# Copy_of_SolderingStation_Control_-_PUMD2.net
KiCad netlist of a schematic drawn in Altium Designer
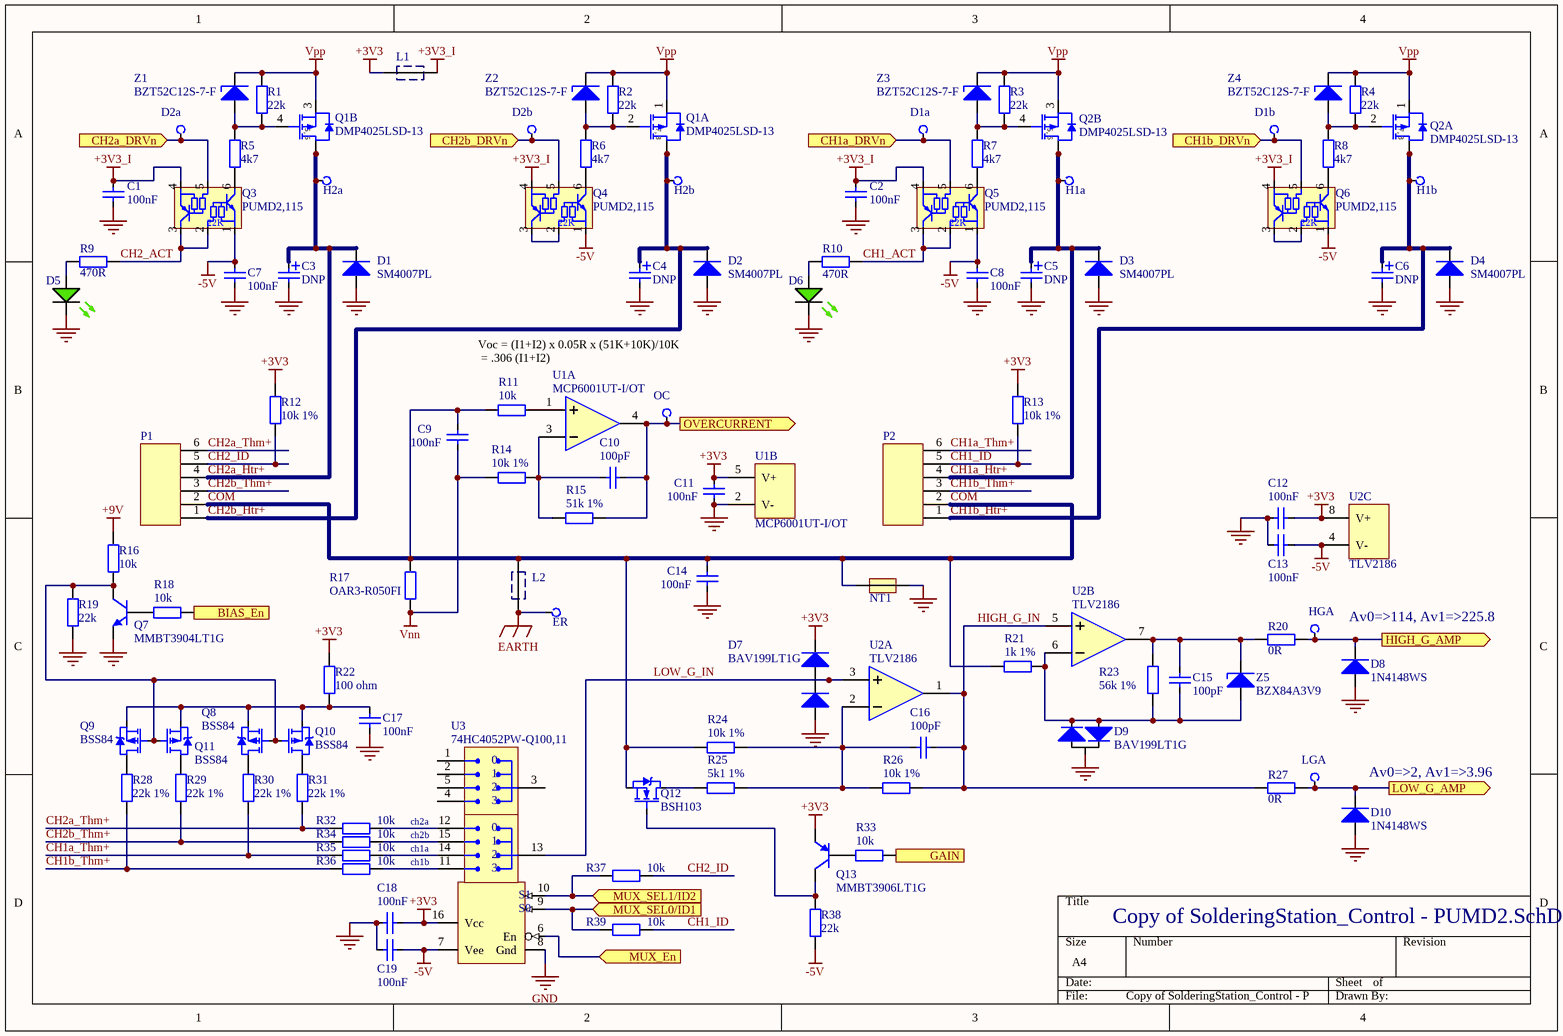
[diagram p0: Copy of SolderingStation_Control - PUMD2.SchDoc]

(export (version "E")
  (design (tool "Eeschema 10.0.6"))
  (components
    (comp (ref "C1")
      (value "100nF")
      (footprint "CCNP1608-0603")
      (description "Capacitor non-polar SMT 0603")
      (fields
        (field (name "MANUFACTURER") "Generic Components")
        (field (name "PUBLISHER") "Altium Hobart Technology Centre")
      )
      (libsource (lib "MyLibrary") (part "Cap_CCNP_0603"))
    )
    (comp (ref "C2")
      (value "100nF")
      (footprint "CCNP1608-0603")
      (description "Capacitor non-polar SMT 0603")
      (fields
        (field (name "MANUFACTURER") "Generic Components")
        (field (name "PUBLISHER") "Altium Hobart Technology Centre")
      )
      (libsource (lib "MyLibrary") (part "Cap_CCNP_0603"))
    )
    (comp (ref "C3")
      (value "DNP")
      (footprint "CC2012-0805")
      (description "Capacitor SMT 0805")
      (fields
        (field (name "MANUFACTURER") "Generic Components")
        (field (name "PUBLISHER") "Altium Hobart Technology Centre")
      )
      (libsource (lib "MyLibrary") (part "Cap_CC_0805"))
    )
    (comp (ref "C4")
      (value "DNP")
      (footprint "CC2012-0805")
      (description "Capacitor SMT 0805")
      (fields
        (field (name "MANUFACTURER") "Generic Components")
        (field (name "PUBLISHER") "Altium Hobart Technology Centre")
      )
      (libsource (lib "MyLibrary") (part "Cap_CC_0805"))
    )
    (comp (ref "C5")
      (value "DNP")
      (footprint "CC2012-0805")
      (description "Capacitor SMT 0805")
      (fields
        (field (name "MANUFACTURER") "Generic Components")
        (field (name "PUBLISHER") "Altium Hobart Technology Centre")
      )
      (libsource (lib "MyLibrary") (part "Cap_CC_0805"))
    )
    (comp (ref "C6")
      (value "DNP")
      (footprint "CC2012-0805")
      (description "Capacitor SMT 0805")
      (fields
        (field (name "MANUFACTURER") "Generic Components")
        (field (name "PUBLISHER") "Altium Hobart Technology Centre")
      )
      (libsource (lib "MyLibrary") (part "Cap_CC_0805"))
    )
    (comp (ref "C7")
      (value "100nF")
      (footprint "CCNP1608-0603")
      (description "Capacitor non-polar SMT 0603")
      (fields
        (field (name "MANUFACTURER") "Generic Components")
        (field (name "PUBLISHER") "Altium Hobart Technology Centre")
      )
      (libsource (lib "MyLibrary") (part "Cap_CCNP_0603"))
    )
    (comp (ref "C8")
      (value "100nF")
      (footprint "CCNP1608-0603")
      (description "Capacitor non-polar SMT 0603")
      (fields
        (field (name "MANUFACTURER") "Generic Components")
        (field (name "PUBLISHER") "Altium Hobart Technology Centre")
      )
      (libsource (lib "MyLibrary") (part "Cap_CCNP_0603"))
    )
    (comp (ref "C9")
      (value "100nF")
      (footprint "CCNP1608-0603")
      (description "Capacitor non-polar SMT 0603")
      (fields
        (field (name "MANUFACTURER") "Generic Components")
        (field (name "PUBLISHER") "Altium Hobart Technology Centre")
      )
      (libsource (lib "MyLibrary") (part "Cap_CCNP_0603"))
    )
    (comp (ref "C10")
      (value "100pF")
      (footprint "CCNP1608-0603")
      (description "Capacitor non-polar SMT 0603")
      (fields
        (field (name "MANUFACTURER") "Generic Components")
        (field (name "PUBLISHER") "Altium Hobart Technology Centre")
      )
      (libsource (lib "MyLibrary") (part "Cap_CCNP_0603"))
    )
    (comp (ref "C11")
      (value "100nF")
      (footprint "CCNP1608-0603")
      (description "Capacitor non-polar SMT 0603")
      (fields
        (field (name "MANUFACTURER") "Generic Components")
        (field (name "PUBLISHER") "Altium Hobart Technology Centre")
      )
      (libsource (lib "MyLibrary") (part "Cap_CCNP_0603"))
    )
    (comp (ref "C12")
      (value "100nF")
      (footprint "CCNP1608-0603")
      (description "Capacitor non-polar SMT 0603")
      (fields
        (field (name "MANUFACTURER") "Generic Components")
        (field (name "PUBLISHER") "Altium Hobart Technology Centre")
      )
      (libsource (lib "MyLibrary") (part "Cap_CCNP_0603"))
    )
    (comp (ref "C13")
      (value "100nF")
      (footprint "CCNP1608-0603")
      (description "Capacitor non-polar SMT 0603")
      (fields
        (field (name "MANUFACTURER") "Generic Components")
        (field (name "PUBLISHER") "Altium Hobart Technology Centre")
      )
      (libsource (lib "MyLibrary") (part "Cap_CCNP_0603"))
    )
    (comp (ref "C14")
      (value "100nF")
      (footprint "CCNP1608-0603")
      (description "Capacitor non-polar SMT 0603")
      (fields
        (field (name "MANUFACTURER") "Generic Components")
        (field (name "PUBLISHER") "Altium Hobart Technology Centre")
      )
      (libsource (lib "MyLibrary") (part "Cap_CCNP_0603"))
    )
    (comp (ref "C15")
      (value "100pF")
      (footprint "CCNP1608-0603")
      (description "Capacitor non-polar SMT 0603")
      (fields
        (field (name "MANUFACTURER") "Generic Components")
        (field (name "PUBLISHER") "Altium Hobart Technology Centre")
      )
      (libsource (lib "MyLibrary") (part "Cap_CCNP_0603"))
    )
    (comp (ref "C16")
      (value "100pF")
      (footprint "CCNP1608-0603")
      (description "Capacitor non-polar SMT 0603")
      (fields
        (field (name "MANUFACTURER") "Generic Components")
        (field (name "PUBLISHER") "Altium Hobart Technology Centre")
      )
      (libsource (lib "MyLibrary") (part "Cap_CCNP_0603"))
    )
    (comp (ref "C17")
      (value "100nF")
      (footprint "CCNP1608-0603")
      (description "Capacitor non-polar SMT 0603")
      (fields
        (field (name "MANUFACTURER") "Generic Components")
        (field (name "PUBLISHER") "Altium Hobart Technology Centre")
      )
      (libsource (lib "MyLibrary") (part "Cap_CCNP_0603"))
    )
    (comp (ref "C18")
      (value "100nF")
      (footprint "CCNP1608-0603")
      (description "Capacitor non-polar SMT 0603")
      (fields
        (field (name "MANUFACTURER") "Generic Components")
        (field (name "PUBLISHER") "Altium Hobart Technology Centre")
      )
      (libsource (lib "MyLibrary") (part "Cap_CCNP_0603"))
    )
    (comp (ref "C19")
      (value "100nF")
      (footprint "CCNP1608-0603")
      (description "Capacitor non-polar SMT 0603")
      (fields
        (field (name "MANUFACTURER") "Generic Components")
        (field (name "PUBLISHER") "Altium Hobart Technology Centre")
      )
      (libsource (lib "MyLibrary") (part "Cap_CCNP_0603"))
    )
    (comp (ref "D1")
      (value "SM4007PL")
      (footprint "SOD-123FL")
      (description "Diodes - General Purpose, 1kV 1A 1.1V 1A SOD-123FL")
      (libsource (lib "MyLibrary") (part "SM4007PL"))
    )
    (comp (ref "D1a")
      (value "Drive1")
      (footprint "PCBPIN - 0.7mm")
      (description "Test Point")
      (libsource (lib "MyLibrary") (part "TP"))
    )
    (comp (ref "D1b")
      (value "Drive2")
      (footprint "PCBPIN - 0.7mm")
      (description "Test Point")
      (libsource (lib "MyLibrary") (part "TP"))
    )
    (comp (ref "D2")
      (value "SM4007PL")
      (footprint "SOD-123FL")
      (description "Diodes - General Purpose, 1kV 1A 1.1V 1A SOD-123FL")
      (libsource (lib "MyLibrary") (part "SM4007PL"))
    )
    (comp (ref "D2a")
      (value "Drive2")
      (footprint "PCBPIN - 0.7mm")
      (description "Test Point")
      (libsource (lib "MyLibrary") (part "TP"))
    )
    (comp (ref "D2b")
      (value "Drive2")
      (footprint "PCBPIN - 0.7mm")
      (description "Test Point")
      (libsource (lib "MyLibrary") (part "TP"))
    )
    (comp (ref "D3")
      (value "SM4007PL")
      (footprint "SOD-123FL")
      (description "Diodes - General Purpose, 1kV 1A 1.1V 1A SOD-123FL")
      (libsource (lib "MyLibrary") (part "SM4007PL"))
    )
    (comp (ref "D4")
      (value "SM4007PL")
      (footprint "SOD-123FL")
      (description "Diodes - General Purpose, 1kV 1A 1.1V 1A SOD-123FL")
      (libsource (lib "MyLibrary") (part "SM4007PL"))
    )
    (comp (ref "D5")
      (value "LED")
      (footprint "LED3MM-GREEN - 10mm Proud")
      (description "3mm Green LED")
      (fields (field (name "MANUFACTURER") "Generic Components") (field (name "PUBLISHER") "Altium Limited"))
      (libsource (lib "MySchLib") (part "LED_3MM_GREEN"))
    )
    (comp (ref "D6")
      (value "LED")
      (footprint "LED3MM-GREEN - 10mm Proud")
      (description "3mm Green LED")
      (fields (field (name "MANUFACTURER") "Generic Components") (field (name "PUBLISHER") "Altium Limited"))
      (libsource (lib "MySchLib") (part "LED_3MM_GREEN"))
    )
    (comp (ref "D7")
      (value "BAV199LT1G")
      (footprint "SOT23_M")
      (description "Dual Series low-leakage switching diodes, 3-Pin SOT-23")
      (libsource (lib "MySchLib") (part "BAV199LT1G"))
    )
    (comp (ref "D8")
      (value "1N4148WS")
      (footprint "SOD-323")
      (description "Switching Diode 100V 150mA 1.25V@150mA 4ns SOD-323")
      (libsource (lib "MyLibrary") (part "1N4148WS"))
    )
    (comp (ref "D9")
      (value "BAV199LT1G")
      (footprint "SOT23_M")
      (description "Dual Series low-leakage switching diodes, 3-Pin SOT-23")
      (libsource (lib "MyLibrary") (part "BAV199LT1G"))
    )
    (comp (ref "D10")
      (value "1N4148WS")
      (footprint "SOD-323")
      (description "Switching Diode 100V 150mA 1.25V@150mA 4ns SOD-323")
      (libsource (lib "MyLibrary") (part "1N4148WS"))
    )
    (comp (ref "ER")
      (value "Gnd")
      (footprint "PCBPIN - 1mm")
      (description "Test Point")
      (libsource (lib "") (part "TP_1"))
    )
    (comp (ref "H1a")
      (value "Heater1")
      (footprint "PCBPIN - 0.7mm")
      (description "Test Point")
      (libsource (lib "") (part "TP_1"))
    )
    (comp (ref "H1b")
      (value "Heater2")
      (footprint "PCBPIN - 0.7mm")
      (description "Test Point")
      (libsource (lib "") (part "TP_1"))
    )
    (comp (ref "H2a")
      (value "Heater2")
      (footprint "PCBPIN - 0.7mm")
      (description "Test Point")
      (libsource (lib "") (part "TP_1"))
    )
    (comp (ref "H2b")
      (value "Heater2")
      (footprint "PCBPIN - 0.7mm")
      (description "Test Point")
      (libsource (lib "") (part "TP_1"))
    )
    (comp (ref "HGA")
      (value "TC1")
      (footprint "PCBPIN - 0.7mm")
      (description "Test Point")
      (libsource (lib "MyLibrary") (part "TP"))
    )
    (comp (ref "L1")
      (value "Ferrite Bead")
      (footprint "FB2012-0805")
      (description "Ferrite Bead SMT 0805, TDK MPZ2012S102AT, 0.15OHM, 1.5A")
      (libsource (lib "MySchLib") (part "Ferrite Bead 0805"))
    )
    (comp (ref "L2")
      (value "Ferrite Bead")
      (footprint "FB2012-0805")
      (description "Ferrite Bead SMT 0805, TDK MPZ2012S102AT, 0.15OHM, 1.5A")
      (libsource (lib "MySchLib") (part "Ferrite Bead 0805"))
    )
    (comp (ref "LGA")
      (value "NTC1")
      (footprint "PCBPIN - 0.7mm")
      (description "Test Point")
      (libsource (lib "MyLibrary") (part "TP"))
    )
    (comp (ref "NT1")
      (value "NetTieVia")
      (footprint "NetTieVia")
      (libsource (lib "MyLibrary") (part "NetTieVia"))
    )
    (comp (ref "OC")
      (value "Overcurrent")
      (footprint "PCBPIN - 0.7mm")
      (description "Test Point")
      (libsource (lib "MyLibrary") (part "TP"))
    )
    (comp (ref "P1")
      (value "MOLEX-43045-0612")
      (footprint "MOLEX-43045-0612")
      (description "Wire-To-Board Connector, With Polarizing Peg, 3 mm, 6 Contacts, Header, Micro-Fit 3.0 43045 Series")
      (libsource (lib "MySchLib") (part "MOLEX-43045-0612"))
    )
    (comp (ref "P2")
      (value "MOLEX-43045-0612")
      (footprint "MOLEX-43045-0612")
      (description "Wire-To-Board Connector, With Polarizing Peg, 3 mm, 6 Contacts, Header, Micro-Fit 3.0 43045 Series")
      (libsource (lib "MySchLib") (part "MOLEX-43045-0612"))
    )
    (comp (ref "Q1")
      (value "DMP4025LSD-13")
      (footprint "SO-8_M")
      (description "P-Channel dual MOSFET, 40 V, 7.6 A, 0.018 ohm, SOIC, Surface Mount")
      (libsource (lib "MyLibrary") (part "DMP4025LSD-13"))
    )
    (comp (ref "Q2")
      (value "DMP4025LSD-13")
      (footprint "SO-8_M")
      (description "P-Channel dual MOSFET, 40 V, 7.6 A, 0.018 ohm, SOIC, Surface Mount")
      (libsource (lib "MyLibrary") (part "DMP4025LSD-13"))
    )
    (comp (ref "Q3")
      (value "PUMD2,115")
      (footprint "SOT363-6M")
      (description "Pre-Biased NPN and PNP pair, 50 V, 100 mA, 22 kohm, 22 kohm")
      (libsource (lib "MySchLib") (part "PUMD2,115"))
    )
    (comp (ref "Q4")
      (value "PUMD2,115")
      (footprint "SOT363-6M")
      (description "Pre-Biased NPN and PNP pair, 50 V, 100 mA, 22 kohm, 22 kohm")
      (libsource (lib "MySchLib") (part "PUMD2,115"))
    )
    (comp (ref "Q5")
      (value "PUMD2,115")
      (footprint "SOT363-6M")
      (description "Pre-Biased NPN and PNP pair, 50 V, 100 mA, 22 kohm, 22 kohm")
      (libsource (lib "MySchLib") (part "PUMD2,115"))
    )
    (comp (ref "Q6")
      (value "PUMD2,115")
      (footprint "SOT363-6M")
      (description "Pre-Biased NPN and PNP pair, 50 V, 100 mA, 22 kohm, 22 kohm")
      (libsource (lib "MySchLib") (part "PUMD2,115"))
    )
    (comp (ref "Q7")
      (value "MMBT3904LT1G")
      (footprint "SOT23_N")
      (description "General Purpose Transistor, NPN Silicon, 3-Pin SOT-23, Pb-Free, Tape and Reel")
      (fields (field (name "MANUFACTURER") "On Semiconductor"))
      (libsource (lib "MyLibrary") (part "MMBT3904LT1G"))
    )
    (comp (ref "Q8")
      (value "BSS84")
      (footprint "SOT23_M")
      (description "P-Channel Enhancement Mode FET -0.13 A, -50 V,  RDS(ON) = 10R at VGS = -5 V")
      (libsource (lib "MySchLib") (part "BSS84"))
    )
    (comp (ref "Q9")
      (value "BSS84")
      (footprint "SOT23_M")
      (description "P-Channel Enhancement Mode FET -0.13 A, -50 V,  RDS(ON) = 10R at VGS = -5 V")
      (libsource (lib "MySchLib") (part "BSS84"))
    )
    (comp (ref "Q10")
      (value "BSS84")
      (footprint "SOT23_M")
      (description "P-Channel Enhancement Mode FET -0.13 A, -50 V,  RDS(ON) = 10R at VGS = -5 V")
      (libsource (lib "MySchLib") (part "BSS84"))
    )
    (comp (ref "Q11")
      (value "BSS84")
      (footprint "SOT23_M")
      (description "P-Channel Enhancement Mode FET -0.13 A, -50 V,  RDS(ON) = 10R at VGS = -5 V")
      (libsource (lib "MySchLib") (part "BSS84"))
    )
    (comp (ref "Q12")
      (value "BSH103")
      (footprint "SOT23_N")
      (description "N-channel enhancement mode FET, , 30 V, 850 mA, 0.4 ohm, SOT23")
      (libsource (lib "MyLibrary") (part "BSH103"))
    )
    (comp (ref "Q13")
      (value "MMBT3906LT1G")
      (footprint "SOT23_N")
      (description "General Purpose Transistor, PNP Silicon, 3-Pin SOT-23, Pb-Free, Tape and Reel")
      (fields (field (name "MANUFACTURER") "On Semiconductor"))
      (libsource (lib "MyLibrary") (part "MMBT3906LT1G"))
    )
    (comp (ref "R1")
      (value "22k")
      (footprint "CR1608-0603_N")
      (description "Resistor SMT 0603")
      (fields
        (field (name "MANUFACTURER") "Generic Components")
        (field (name "PUBLISHER") "Altium Hobart Technology Centre")
      )
      (libsource (lib "MyLibrary") (part "Res_CR0603"))
    )
    (comp (ref "R2")
      (value "22k")
      (footprint "CR1608-0603_N")
      (description "Resistor SMT 0603")
      (fields
        (field (name "MANUFACTURER") "Generic Components")
        (field (name "PUBLISHER") "Altium Hobart Technology Centre")
      )
      (libsource (lib "MyLibrary") (part "Res_CR0603"))
    )
    (comp (ref "R3")
      (value "22k")
      (footprint "CR1608-0603_N")
      (description "Resistor SMT 0603")
      (fields
        (field (name "MANUFACTURER") "Generic Components")
        (field (name "PUBLISHER") "Altium Hobart Technology Centre")
      )
      (libsource (lib "MyLibrary") (part "Res_CR0603"))
    )
    (comp (ref "R4")
      (value "22k")
      (footprint "CR1608-0603_N")
      (description "Resistor SMT 0603")
      (fields
        (field (name "MANUFACTURER") "Generic Components")
        (field (name "PUBLISHER") "Altium Hobart Technology Centre")
      )
      (libsource (lib "MyLibrary") (part "Res_CR0603"))
    )
    (comp (ref "R5")
      (value "4k7")
      (footprint "CR1608-0603_N")
      (description "Resistor SMT 0603")
      (fields
        (field (name "MANUFACTURER") "Generic Components")
        (field (name "PUBLISHER") "Altium Hobart Technology Centre")
      )
      (libsource (lib "MyLibrary") (part "Res_CR0603"))
    )
    (comp (ref "R6")
      (value "4k7")
      (footprint "CR1608-0603_N")
      (description "Resistor SMT 0603")
      (fields
        (field (name "MANUFACTURER") "Generic Components")
        (field (name "PUBLISHER") "Altium Hobart Technology Centre")
      )
      (libsource (lib "MyLibrary") (part "Res_CR0603"))
    )
    (comp (ref "R7")
      (value "4k7")
      (footprint "CR1608-0603_N")
      (description "Resistor SMT 0603")
      (fields
        (field (name "MANUFACTURER") "Generic Components")
        (field (name "PUBLISHER") "Altium Hobart Technology Centre")
      )
      (libsource (lib "MyLibrary") (part "Res_CR0603"))
    )
    (comp (ref "R8")
      (value "4k7")
      (footprint "CR1608-0603_N")
      (description "Resistor SMT 0603")
      (fields
        (field (name "MANUFACTURER") "Generic Components")
        (field (name "PUBLISHER") "Altium Hobart Technology Centre")
      )
      (libsource (lib "MyLibrary") (part "Res_CR0603"))
    )
    (comp (ref "R9")
      (value "470R")
      (footprint "CR1608-0603_N")
      (description "Resistor SMT 0603")
      (fields
        (field (name "MANUFACTURER") "Generic Components")
        (field (name "PUBLISHER") "Altium Hobart Technology Centre")
      )
      (libsource (lib "") (part "Res_CR0603_2"))
    )
    (comp (ref "R10")
      (value "470R")
      (footprint "CR1608-0603_N")
      (description "Resistor SMT 0603")
      (fields
        (field (name "MANUFACTURER") "Generic Components")
        (field (name "PUBLISHER") "Altium Hobart Technology Centre")
      )
      (libsource (lib "") (part "Res_CR0603_2"))
    )
    (comp (ref "R11")
      (value "10k")
      (footprint "CR1608-0603_N")
      (description "Resistor SMT 0603")
      (fields
        (field (name "MANUFACTURER") "Generic Components")
        (field (name "PUBLISHER") "Altium Hobart Technology Centre")
      )
      (libsource (lib "") (part "Res_CR0603_3"))
    )
    (comp (ref "R12")
      (value "10k 1%")
      (footprint "CR1608-0603_N")
      (description "Resistor SMT 0603")
      (fields
        (field (name "MANUFACTURER") "Generic Components")
        (field (name "PUBLISHER") "Altium Hobart Technology Centre")
      )
      (libsource (lib "MyLibrary") (part "Res_CR0603"))
    )
    (comp (ref "R13")
      (value "10k 1%")
      (footprint "CR1608-0603_N")
      (description "Resistor SMT 0603")
      (fields
        (field (name "MANUFACTURER") "Generic Components")
        (field (name "PUBLISHER") "Altium Hobart Technology Centre")
      )
      (libsource (lib "MyLibrary") (part "Res_CR0603"))
    )
    (comp (ref "R14")
      (value "10k 1%")
      (footprint "CR1608-0603_N")
      (description "Resistor SMT 0603")
      (fields
        (field (name "MANUFACTURER") "Generic Components")
        (field (name "PUBLISHER") "Altium Hobart Technology Centre")
      )
      (libsource (lib "") (part "Res_CR0603_3"))
    )
    (comp (ref "R15")
      (value "51k 1%")
      (footprint "CR1608-0603_N")
      (description "Resistor SMT 0603")
      (fields
        (field (name "MANUFACTURER") "Generic Components")
        (field (name "PUBLISHER") "Altium Hobart Technology Centre")
      )
      (libsource (lib "") (part "Res_CR0603_2"))
    )
    (comp (ref "R16")
      (value "10k")
      (footprint "CR1608-0603_N")
      (description "Resistor SMT 0603")
      (fields
        (field (name "MANUFACTURER") "Generic Components")
        (field (name "PUBLISHER") "Altium Hobart Technology Centre")
      )
      (libsource (lib "") (part "Res_CR0603_1"))
    )
    (comp (ref "R17")
      (value "OAR3-R050FI")
      (footprint "OAR3-R050FI")
      (description "Current Sense Resistor, 0.05 ohm, OAR Series, 3 W, Metal Strip, Radial Leaded, 1%")
      (libsource (lib "MySchLib") (part "OAR3-R050FI"))
    )
    (comp (ref "R18")
      (value "10k")
      (footprint "CR1608-0603_N")
      (description "Resistor SMT 0603")
      (fields
        (field (name "MANUFACTURER") "Generic Components")
        (field (name "PUBLISHER") "Altium Hobart Technology Centre")
      )
      (libsource (lib "") (part "Res_CR0603_2"))
    )
    (comp (ref "R19")
      (value "22k")
      (footprint "CR1608-0603_N")
      (description "Resistor SMT 0603")
      (fields
        (field (name "MANUFACTURER") "Generic Components")
        (field (name "PUBLISHER") "Altium Hobart Technology Centre")
      )
      (libsource (lib "MyLibrary") (part "Res_CR0603"))
    )
    (comp (ref "R20")
      (value "0R")
      (footprint "CR1608-0603_N")
      (description "Resistor SMT 0603")
      (fields
        (field (name "MANUFACTURER") "Generic Components")
        (field (name "PUBLISHER") "Altium Hobart Technology Centre")
      )
      (libsource (lib "") (part "Res_CR0603_1"))
    )
    (comp (ref "R21")
      (value "1k 1%")
      (footprint "CR1608-0603_N")
      (description "Resistor SMT 0603")
      (fields
        (field (name "MANUFACTURER") "Generic Components")
        (field (name "PUBLISHER") "Altium Hobart Technology Centre")
      )
      (libsource (lib "") (part "Res_CR0603_3"))
    )
    (comp (ref "R22")
      (value "100 ohm")
      (footprint "CR1608-0603_N")
      (description "Resistor SMT 0603")
      (fields
        (field (name "MANUFACTURER") "Generic Components")
        (field (name "PUBLISHER") "Altium Hobart Technology Centre")
      )
      (libsource (lib "") (part "Res_CR0603_3"))
    )
    (comp (ref "R23")
      (value "56k 1%")
      (footprint "CR1608-0603_N")
      (description "Resistor SMT 0603")
      (fields
        (field (name "MANUFACTURER") "Generic Components")
        (field (name "PUBLISHER") "Altium Hobart Technology Centre")
      )
      (libsource (lib "MyLibrary") (part "Res_CR0603"))
    )
    (comp (ref "R24")
      (value "10k 1%")
      (footprint "CR1608-0603_N")
      (description "Resistor SMT 0603")
      (fields
        (field (name "MANUFACTURER") "Generic Components")
        (field (name "PUBLISHER") "Altium Hobart Technology Centre")
      )
      (libsource (lib "") (part "Res_CR0603_2"))
    )
    (comp (ref "R25")
      (value "5k1 1%")
      (footprint "CR1608-0603_N")
      (description "Resistor SMT 0603")
      (fields
        (field (name "MANUFACTURER") "Generic Components")
        (field (name "PUBLISHER") "Altium Hobart Technology Centre")
      )
      (libsource (lib "") (part "Res_CR0603_1"))
    )
    (comp (ref "R26")
      (value "10k 1%")
      (footprint "CR1608-0603_N")
      (description "Resistor SMT 0603")
      (fields
        (field (name "MANUFACTURER") "Generic Components")
        (field (name "PUBLISHER") "Altium Hobart Technology Centre")
      )
      (libsource (lib "") (part "Res_CR0603_2"))
    )
    (comp (ref "R27")
      (value "0R")
      (footprint "CR1608-0603_N")
      (description "Resistor SMT 0603")
      (fields
        (field (name "MANUFACTURER") "Generic Components")
        (field (name "PUBLISHER") "Altium Hobart Technology Centre")
      )
      (libsource (lib "") (part "Res_CR0603_1"))
    )
    (comp (ref "R28")
      (value "22k 1%")
      (footprint "CR1608-0603_N")
      (description "Resistor SMT 0603")
      (fields
        (field (name "MANUFACTURER") "Generic Components")
        (field (name "PUBLISHER") "Altium Hobart Technology Centre")
      )
      (libsource (lib "") (part "Res_CR0603_2"))
    )
    (comp (ref "R29")
      (value "22k 1%")
      (footprint "CR1608-0603_N")
      (description "Resistor SMT 0603")
      (fields
        (field (name "MANUFACTURER") "Generic Components")
        (field (name "PUBLISHER") "Altium Hobart Technology Centre")
      )
      (libsource (lib "") (part "Res_CR0603_2"))
    )
    (comp (ref "R30")
      (value "22k 1%")
      (footprint "CR1608-0603_N")
      (description "Resistor SMT 0603")
      (fields
        (field (name "MANUFACTURER") "Generic Components")
        (field (name "PUBLISHER") "Altium Hobart Technology Centre")
      )
      (libsource (lib "MyLibrary") (part "Res_CR0603"))
    )
    (comp (ref "R31")
      (value "22k 1%")
      (footprint "CR1608-0603_N")
      (description "Resistor SMT 0603")
      (fields
        (field (name "MANUFACTURER") "Generic Components")
        (field (name "PUBLISHER") "Altium Hobart Technology Centre")
      )
      (libsource (lib "MyLibrary") (part "Res_CR0603"))
    )
    (comp (ref "R32")
      (value "10k")
      (footprint "CR1608-0603_N")
      (description "Resistor SMT 0603")
      (fields
        (field (name "MANUFACTURER") "Generic Components")
        (field (name "PUBLISHER") "Altium Hobart Technology Centre")
      )
      (libsource (lib "") (part "Res_CR0603_1"))
    )
    (comp (ref "R33")
      (value "10k")
      (footprint "CR1608-0603_N")
      (description "Resistor SMT 0603")
      (fields
        (field (name "MANUFACTURER") "Generic Components")
        (field (name "PUBLISHER") "Altium Hobart Technology Centre")
      )
      (libsource (lib "") (part "Res_CR0603_2"))
    )
    (comp (ref "R34")
      (value "10k")
      (footprint "CR1608-0603_N")
      (description "Resistor SMT 0603")
      (fields
        (field (name "MANUFACTURER") "Generic Components")
        (field (name "PUBLISHER") "Altium Hobart Technology Centre")
      )
      (libsource (lib "") (part "Res_CR0603_1"))
    )
    (comp (ref "R35")
      (value "10k")
      (footprint "CR1608-0603_N")
      (description "Resistor SMT 0603")
      (fields
        (field (name "MANUFACTURER") "Generic Components")
        (field (name "PUBLISHER") "Altium Hobart Technology Centre")
      )
      (libsource (lib "") (part "Res_CR0603_1"))
    )
    (comp (ref "R36")
      (value "10k")
      (footprint "CR1608-0603_N")
      (description "Resistor SMT 0603")
      (fields
        (field (name "MANUFACTURER") "Generic Components")
        (field (name "PUBLISHER") "Altium Hobart Technology Centre")
      )
      (libsource (lib "") (part "Res_CR0603_1"))
    )
    (comp (ref "R37")
      (value "10k")
      (footprint "CR1608-0603_N")
      (description "Resistor SMT 0603")
      (fields
        (field (name "MANUFACTURER") "Generic Components")
        (field (name "PUBLISHER") "Altium Hobart Technology Centre")
      )
      (libsource (lib "") (part "Res_CR0603_1"))
    )
    (comp (ref "R38")
      (value "22k")
      (footprint "CR1608-0603_N")
      (description "Resistor SMT 0603")
      (fields
        (field (name "MANUFACTURER") "Generic Components")
        (field (name "PUBLISHER") "Altium Hobart Technology Centre")
      )
      (libsource (lib "MyLibrary") (part "Res_CR0603"))
    )
    (comp (ref "R39")
      (value "10k")
      (footprint "CR1608-0603_N")
      (description "Resistor SMT 0603")
      (fields
        (field (name "MANUFACTURER") "Generic Components")
        (field (name "PUBLISHER") "Altium Hobart Technology Centre")
      )
      (libsource (lib "") (part "Res_CR0603_1"))
    )
    (comp (ref "U1")
      (value "MCP6001UT-I/OT")
      (footprint "SOT23-5_M")
      (description "Op-Amp, Single supply R-R in/out")
      (libsource (lib "") (part "MCP6001UT-I/OT_1"))
    )
    (comp (ref "U2")
      (value "TLV2186")
      (footprint "SOIC127P600-8M")
      (description "Dual Precision,Rail-to-Rail Input and Output, 4.5-24V, Zero-Drift OperationalAmplifier")
      (libsource (lib "MySchLib") (part "TLV2186"))
    )
    (comp (ref "U3")
      (value "74HC4052PW-Q100,11")
      (footprint "TSSOP16_M")
      (description "Analog Multiplexer / Demultiplexer, 4:1, 2 Circuits, 225 ohm, 2V to 10V, TSSOP-16")
      (libsource (lib "MySchLib") (part "74HC4052PW-Q100,11"))
    )
    (comp (ref "Z1")
      (value "BZT52C12S-7-F")
      (footprint "SOD-323")
      (description "Surface Mount Zener Diode, 12-13 V, -65 to 150 degC, SOD-123")
      (libsource (lib "MySchLib") (part "BZT52C12S-7-F"))
    )
    (comp (ref "Z2")
      (value "BZT52C12S-7-F")
      (footprint "SOD-323")
      (description "Surface Mount Zener Diode, 12-13 V, -65 to 150 degC, SOD-123")
      (libsource (lib "MySchLib") (part "BZT52C12S-7-F"))
    )
    (comp (ref "Z3")
      (value "BZT52C12S-7-F")
      (footprint "SOD-323")
      (description "Surface Mount Zener Diode, 12-13 V, -65 to 150 degC, SOD-123")
      (libsource (lib "MySchLib") (part "BZT52C12S-7-F"))
    )
    (comp (ref "Z4")
      (value "BZT52C12S-7-F")
      (footprint "SOD-323")
      (description "Surface Mount Zener Diode, 12-13 V, -65 to 150 degC, SOD-123")
      (libsource (lib "MySchLib") (part "BZT52C12S-7-F"))
    )
    (comp (ref "Z5")
      (value "BZX84A3V9")
      (footprint "SOT23_M")
      (description "Zener Diode, 3.9V, 250mW, SOT-23, 1%, 150C")
      (fields
        (field (name "MANUFACTURER") "Generic Components")
        (field (name "PUBLISHER") "Altium Hobart Technology Centre")
      )
      (libsource (lib "MyLibrary") (part "BZX84A3V9"))
    )
  )
  (nets
    (net (code "1") (name "+3V3") (class "Default")
      (node (ref "C11") (pin "1") (pinfunction "1_1") (pintype "passive"))
      (node (ref "C12") (pin "1") (pinfunction "1_1") (pintype "passive"))
      (node (ref "C18") (pin "1") (pinfunction "1_1") (pintype "passive"))
      (node (ref "D7") (pin "2") (pinfunction "A2_2") (pintype "passive"))
      (node (ref "L1") (pin "1") (pinfunction "1_1") (pintype "passive"))
      (node (ref "Q13") (pin "2") (pinfunction "E_2") (pintype "passive"))
      (node (ref "R12") (pin "2") (pinfunction "2_2") (pintype "passive"))
      (node (ref "R13") (pin "2") (pinfunction "2_2") (pintype "passive"))
      (node (ref "R22") (pin "1") (pinfunction "1_1") (pintype "passive"))
      (node (ref "U1") (pin "5") (pinfunction "V+_5") (pintype "power_in"))
      (node (ref "U2") (pin "8") (pinfunction "V+_8") (pintype "power_in"))
      (node (ref "U3") (pin "16") (pinfunction "Vcc_16") (pintype "power_in"))
    )
    (net (code "2") (name "+3V3_I") (class "Default")
      (node (ref "C1") (pin "1") (pinfunction "1_1") (pintype "passive"))
      (node (ref "C2") (pin "1") (pinfunction "1_1") (pintype "passive"))
      (node (ref "L1") (pin "2") (pinfunction "2_2") (pintype "passive"))
      (node (ref "Q3") (pin "4") (pinfunction "E2_4") (pintype "passive"))
      (node (ref "Q4") (pin "4") (pinfunction "E2_4") (pintype "passive"))
      (node (ref "Q5") (pin "4") (pinfunction "E2_4") (pintype "passive"))
      (node (ref "Q6") (pin "4") (pinfunction "E2_4") (pintype "passive"))
    )
    (net (code "3") (name "+9V") (class "Default")
      (node (ref "R16") (pin "1") (pinfunction "1_1") (pintype "passive"))
    )
    (net (code "4") (name "-5V") (class "Default")
      (node (ref "C13") (pin "1") (pinfunction "1_1") (pintype "passive"))
      (node (ref "C19") (pin "1") (pinfunction "1_1") (pintype "passive"))
      (node (ref "C7") (pin "1") (pinfunction "1_1") (pintype "passive"))
      (node (ref "C8") (pin "1") (pinfunction "1_1") (pintype "passive"))
      (node (ref "Q3") (pin "1") (pinfunction "E1_1") (pintype "passive"))
      (node (ref "Q4") (pin "1") (pinfunction "E1_1") (pintype "passive"))
      (node (ref "Q5") (pin "1") (pinfunction "E1_1") (pintype "passive"))
      (node (ref "Q6") (pin "1") (pinfunction "E1_1") (pintype "passive"))
      (node (ref "R38") (pin "1") (pinfunction "1_1") (pintype "passive"))
      (node (ref "U2") (pin "4") (pinfunction "V-_4") (pintype "power_in"))
      (node (ref "U3") (pin "7") (pinfunction "Vee_7") (pintype "power_in"))
    )
    (net (code "5") (name "/BIAS_En") (class "Default")
      (node (ref "R18") (pin "2") (pinfunction "2_2") (pintype "passive"))
    )
    (net (code "6") (name "/CH1_ACT") (class "Default")
      (node (ref "Q5") (pin "2") (pinfunction "B1_2") (pintype "passive"))
      (node (ref "Q5") (pin "3") (pinfunction "C2_3") (pintype "passive"))
      (node (ref "R10") (pin "2") (pinfunction "2_2") (pintype "passive"))
    )
    (net (code "7") (name "/CH1_ID") (class "Default")
      (node (ref "P2") (pin "5") (pinfunction "5_5") (pintype "passive"))
      (node (ref "R13") (pin "1") (pinfunction "1_1") (pintype "passive"))
      (node (ref "R39") (pin "1") (pinfunction "1_1") (pintype "passive"))
    )
    (net (code "8") (name "/CH1a_DRVn") (class "Default")
      (node (ref "D1a") (pin "1") (pinfunction "TP_1") (pintype "passive"))
      (node (ref "Q5") (pin "5") (pinfunction "B2_5") (pintype "passive"))
    )
    (net (code "9") (name "/CH1a_Htr+") (class "Default")
      (node (ref "C5") (pin "1") (pinfunction "1_1") (pintype "passive"))
      (node (ref "D3") (pin "K") (pinfunction "K_K") (pintype "passive"))
      (node (ref "H1a") (pin "1") (pinfunction "TP_1") (pintype "passive"))
      (node (ref "P2") (pin "4") (pinfunction "4_4") (pintype "passive"))
      (node (ref "Q2") (pin "5") (pinfunction "D2_5") (pintype "passive"))
      (node (ref "Q2") (pin "6") (pinfunction "D2_6") (pintype "passive"))
    )
    (net (code "10") (name "/CH1a_Thm+") (class "Default")
      (node (ref "P2") (pin "6") (pinfunction "6_6") (pintype "passive"))
      (node (ref "R30") (pin "1") (pinfunction "1_1") (pintype "passive"))
      (node (ref "R35") (pin "2") (pinfunction "2_2") (pintype "passive"))
    )
    (net (code "11") (name "/CH1b_DRVn") (class "Default")
      (node (ref "D1b") (pin "1") (pinfunction "TP_1") (pintype "passive"))
      (node (ref "Q6") (pin "5") (pinfunction "B2_5") (pintype "passive"))
    )
    (net (code "12") (name "/CH1b_Htr+") (class "Default")
      (node (ref "C6") (pin "1") (pinfunction "1_1") (pintype "passive"))
      (node (ref "D4") (pin "K") (pinfunction "K_K") (pintype "passive"))
      (node (ref "H1b") (pin "1") (pinfunction "TP_1") (pintype "passive"))
      (node (ref "P2") (pin "1") (pinfunction "1_1") (pintype "passive"))
      (node (ref "Q2") (pin "7") (pinfunction "D1_7") (pintype "passive"))
      (node (ref "Q2") (pin "8") (pinfunction "D1_8") (pintype "passive"))
    )
    (net (code "13") (name "/CH1b_Thm+") (class "Default")
      (node (ref "P2") (pin "3") (pinfunction "3_3") (pintype "passive"))
      (node (ref "R28") (pin "1") (pinfunction "1_1") (pintype "passive"))
      (node (ref "R36") (pin "2") (pinfunction "2_2") (pintype "passive"))
    )
    (net (code "14") (name "/CH2_ACT") (class "Default")
      (node (ref "Q3") (pin "2") (pinfunction "B1_2") (pintype "passive"))
      (node (ref "Q3") (pin "3") (pinfunction "C2_3") (pintype "passive"))
      (node (ref "R9") (pin "2") (pinfunction "2_2") (pintype "passive"))
    )
    (net (code "15") (name "/CH2_ID") (class "Default")
      (node (ref "P1") (pin "5") (pinfunction "5_5") (pintype "passive"))
      (node (ref "R12") (pin "1") (pinfunction "1_1") (pintype "passive"))
      (node (ref "R37") (pin "1") (pinfunction "1_1") (pintype "passive"))
    )
    (net (code "16") (name "/CH2a_DRVn") (class "Default")
      (node (ref "D2a") (pin "1") (pinfunction "TP_1") (pintype "passive"))
      (node (ref "Q3") (pin "5") (pinfunction "B2_5") (pintype "passive"))
    )
    (net (code "17") (name "/CH2a_Htr+") (class "Default")
      (node (ref "C3") (pin "1") (pinfunction "1_1") (pintype "passive"))
      (node (ref "D1") (pin "K") (pinfunction "K_K") (pintype "passive"))
      (node (ref "H2a") (pin "1") (pinfunction "TP_1") (pintype "passive"))
      (node (ref "P1") (pin "4") (pinfunction "4_4") (pintype "passive"))
      (node (ref "Q1") (pin "5") (pinfunction "D2_5") (pintype "passive"))
      (node (ref "Q1") (pin "6") (pinfunction "D2_6") (pintype "passive"))
    )
    (net (code "18") (name "/CH2a_Thm+") (class "Default")
      (node (ref "P1") (pin "6") (pinfunction "6_6") (pintype "passive"))
      (node (ref "R31") (pin "1") (pinfunction "1_1") (pintype "passive"))
      (node (ref "R32") (pin "2") (pinfunction "2_2") (pintype "passive"))
    )
    (net (code "19") (name "/CH2b_DRVn") (class "Default")
      (node (ref "D2b") (pin "1") (pinfunction "TP_1") (pintype "passive"))
      (node (ref "Q4") (pin "5") (pinfunction "B2_5") (pintype "passive"))
    )
    (net (code "20") (name "/CH2b_Htr+") (class "Default")
      (node (ref "C4") (pin "1") (pinfunction "1_1") (pintype "passive"))
      (node (ref "D2") (pin "K") (pinfunction "K_K") (pintype "passive"))
      (node (ref "H2b") (pin "1") (pinfunction "TP_1") (pintype "passive"))
      (node (ref "P1") (pin "1") (pinfunction "1_1") (pintype "passive"))
      (node (ref "Q1") (pin "7") (pinfunction "D1_7") (pintype "passive"))
      (node (ref "Q1") (pin "8") (pinfunction "D1_8") (pintype "passive"))
    )
    (net (code "21") (name "/CH2b_Thm+") (class "Default")
      (node (ref "P1") (pin "3") (pinfunction "3_3") (pintype "passive"))
      (node (ref "R29") (pin "1") (pinfunction "1_1") (pintype "passive"))
      (node (ref "R34") (pin "2") (pinfunction "2_2") (pintype "passive"))
    )
    (net (code "22") (name "/COM") (class "Default")
      (node (ref "C14") (pin "1") (pinfunction "1_1") (pintype "passive"))
      (node (ref "C9") (pin "1") (pinfunction "1_1") (pintype "passive"))
      (node (ref "L2") (pin "2") (pinfunction "2_2") (pintype "passive"))
      (node (ref "NT1") (pin "2") (pinfunction "2_2") (pintype "passive"))
      (node (ref "P1") (pin "2") (pinfunction "2_2") (pintype "passive"))
      (node (ref "P2") (pin "2") (pinfunction "2_2") (pintype "passive"))
      (node (ref "Q12") (pin "2") (pinfunction "S_2") (pintype "passive"))
      (node (ref "R11") (pin "2") (pinfunction "2_2") (pintype "passive"))
      (node (ref "R17") (pin "2") (pinfunction "2_2") (pintype "passive"))
      (node (ref "R21") (pin "2") (pinfunction "2_2") (pintype "passive"))
      (node (ref "R24") (pin "1") (pinfunction "1_1") (pintype "passive"))
    )
    (net (code "23") (name "/GAIN") (class "Default")
      (node (ref "R33") (pin "2") (pinfunction "2_2") (pintype "passive"))
    )
    (net (code "24") (name "/HIGH_G_AMP") (class "Default")
      (node (ref "D8") (pin "K") (pinfunction "K_K") (pintype "passive"))
      (node (ref "HGA") (pin "1") (pinfunction "TP_1") (pintype "passive"))
      (node (ref "R20") (pin "1") (pinfunction "1_1") (pintype "passive"))
    )
    (net (code "25") (name "/HIGH_G_IN") (class "Default")
      (node (ref "C16") (pin "2") (pinfunction "2_2") (pintype "passive"))
      (node (ref "R26") (pin "2") (pinfunction "2_2") (pintype "passive"))
      (node (ref "R27") (pin "2") (pinfunction "2_2") (pintype "passive"))
      (node (ref "U2") (pin "1") (pinfunction "A_1") (pintype "passive"))
      (node (ref "U2") (pin "5") (pinfunction "B+_5") (pintype "passive"))
    )
    (net (code "26") (name "/LOW_G_AMP") (class "Default")
      (node (ref "D10") (pin "K") (pinfunction "K_K") (pintype "passive"))
      (node (ref "LGA") (pin "1") (pinfunction "TP_1") (pintype "passive"))
      (node (ref "R27") (pin "1") (pinfunction "1_1") (pintype "passive"))
    )
    (net (code "27") (name "/LOW_G_IN") (class "Default")
      (node (ref "D7") (pin "3") (pinfunction "K_3") (pintype "passive"))
      (node (ref "U2") (pin "3") (pinfunction "A+_3") (pintype "passive"))
      (node (ref "U3") (pin "13") (pinfunction "1Z_13") (pintype "passive"))
    )
    (net (code "28") (name "/MUX_En") (class "Default")
      (node (ref "U3") (pin "6") (pinfunction "En_6") (pintype "input"))
    )
    (net (code "29") (name "/MUX_SEL0{slash}ID1") (class "Default")
      (node (ref "R39") (pin "2") (pinfunction "2_2") (pintype "passive"))
      (node (ref "U3") (pin "9") (pinfunction "S1_9") (pintype "input"))
    )
    (net (code "30") (name "/MUX_SEL1{slash}ID2") (class "Default")
      (node (ref "R37") (pin "2") (pinfunction "2_2") (pintype "passive"))
      (node (ref "U3") (pin "10") (pinfunction "S0_10") (pintype "input"))
    )
    (net (code "31") (name "/OVERCURRENT") (class "Default")
      (node (ref "C10") (pin "2") (pinfunction "2_2") (pintype "passive"))
      (node (ref "OC") (pin "1") (pinfunction "TP_1") (pintype "passive"))
      (node (ref "R15") (pin "2") (pinfunction "2_2") (pintype "passive"))
      (node (ref "U1") (pin "4") (pinfunction "Out_4") (pintype "passive"))
    )
    (net (code "32") (name "EARTH") (class "Default")
      (node (ref "ER") (pin "1") (pinfunction "TP_1") (pintype "passive"))
      (node (ref "L2") (pin "1") (pinfunction "1_1") (pintype "passive"))
    )
    (net (code "33") (name "GND") (class "Default")
      (node (ref "C1") (pin "2") (pinfunction "2_2") (pintype "passive"))
      (node (ref "C11") (pin "2") (pinfunction "2_2") (pintype "passive"))
      (node (ref "C12") (pin "2") (pinfunction "2_2") (pintype "passive"))
      (node (ref "C13") (pin "2") (pinfunction "2_2") (pintype "passive"))
      (node (ref "C14") (pin "2") (pinfunction "2_2") (pintype "passive"))
      (node (ref "C17") (pin "1") (pinfunction "1_1") (pintype "passive"))
      (node (ref "C18") (pin "2") (pinfunction "2_2") (pintype "passive"))
      (node (ref "C19") (pin "2") (pinfunction "2_2") (pintype "passive"))
      (node (ref "C2") (pin "2") (pinfunction "2_2") (pintype "passive"))
      (node (ref "C3") (pin "2") (pinfunction "2_2") (pintype "passive"))
      (node (ref "C4") (pin "2") (pinfunction "2_2") (pintype "passive"))
      (node (ref "C5") (pin "2") (pinfunction "2_2") (pintype "passive"))
      (node (ref "C6") (pin "2") (pinfunction "2_2") (pintype "passive"))
      (node (ref "C7") (pin "2") (pinfunction "2_2") (pintype "passive"))
      (node (ref "C8") (pin "2") (pinfunction "2_2") (pintype "passive"))
      (node (ref "D1") (pin "A") (pinfunction "A_A") (pintype "passive"))
      (node (ref "D10") (pin "A") (pinfunction "A_A") (pintype "passive"))
      (node (ref "D2") (pin "A") (pinfunction "A_A") (pintype "passive"))
      (node (ref "D3") (pin "A") (pinfunction "A_A") (pintype "passive"))
      (node (ref "D4") (pin "A") (pinfunction "A_A") (pintype "passive"))
      (node (ref "D5") (pin "K") (pinfunction "K_K") (pintype "passive"))
      (node (ref "D6") (pin "K") (pinfunction "K_K") (pintype "passive"))
      (node (ref "D7") (pin "1") (pinfunction "A1_1") (pintype "passive"))
      (node (ref "D8") (pin "A") (pinfunction "A_A") (pintype "passive"))
      (node (ref "D9") (pin "3") (pinfunction "K_3") (pintype "passive"))
      (node (ref "NT1") (pin "1") (pinfunction "1_1") (pintype "passive"))
      (node (ref "Q7") (pin "2") (pinfunction "E_2") (pintype "passive"))
      (node (ref "R19") (pin "1") (pinfunction "1_1") (pintype "passive"))
      (node (ref "U1") (pin "2") (pinfunction "V-_2") (pintype "power_in"))
      (node (ref "U3") (pin "8") (pinfunction "Gnd_8") (pintype "power_in"))
    )
    (net (code "34") (name "Net-(C15-Pad2)") (class "Default")
      (node (ref "C15") (pin "2") (pinfunction "2_2") (pintype "passive"))
      (node (ref "R20") (pin "2") (pinfunction "2_2") (pintype "passive"))
      (node (ref "R23") (pin "2") (pinfunction "2_2") (pintype "passive"))
      (node (ref "U2") (pin "7") (pinfunction "7_7") (pintype "passive"))
      (node (ref "Z5") (pin "K") (pinfunction "K_K") (pintype "passive"))
    )
    (net (code "35") (name "Net-(D5-PadA)") (class "Default")
      (node (ref "D5") (pin "A") (pinfunction "A_A") (pintype "passive"))
      (node (ref "R9") (pin "1") (pinfunction "1_1") (pintype "passive"))
    )
    (net (code "36") (name "Net-(D6-PadA)") (class "Default")
      (node (ref "D6") (pin "A") (pinfunction "A_A") (pintype "passive"))
      (node (ref "R10") (pin "1") (pinfunction "1_1") (pintype "passive"))
    )
    (net (code "37") (name "Net-(D9-A1)") (class "Default")
      (node (ref "C15") (pin "1") (pinfunction "1_1") (pintype "passive"))
      (node (ref "D9") (pin "1") (pinfunction "A1_1") (pintype "passive"))
      (node (ref "D9") (pin "2") (pinfunction "A2_2") (pintype "passive"))
      (node (ref "R21") (pin "1") (pinfunction "1_1") (pintype "passive"))
      (node (ref "R23") (pin "1") (pinfunction "1_1") (pintype "passive"))
      (node (ref "U2") (pin "6") (pinfunction "B-_6") (pintype "passive"))
      (node (ref "Z5") (pin "A") (pinfunction "A_A") (pintype "passive"))
    )
    (net (code "38") (name "Net-(Q1A-G1)") (class "Default")
      (node (ref "Q1") (pin "2") (pinfunction "G1_2") (pintype "passive"))
      (node (ref "R2") (pin "1") (pinfunction "1_1") (pintype "passive"))
      (node (ref "R6") (pin "2") (pinfunction "2_2") (pintype "passive"))
      (node (ref "Z2") (pin "A") (pinfunction "A_A") (pintype "passive"))
    )
    (net (code "39") (name "Net-(Q1B-G2)") (class "Default")
      (node (ref "Q1") (pin "4") (pinfunction "G2_4") (pintype "passive"))
      (node (ref "R1") (pin "1") (pinfunction "1_1") (pintype "passive"))
      (node (ref "R5") (pin "2") (pinfunction "2_2") (pintype "passive"))
      (node (ref "Z1") (pin "A") (pinfunction "A_A") (pintype "passive"))
    )
    (net (code "40") (name "Net-(Q2A-G1)") (class "Default")
      (node (ref "Q2") (pin "2") (pinfunction "G1_2") (pintype "passive"))
      (node (ref "R4") (pin "1") (pinfunction "1_1") (pintype "passive"))
      (node (ref "R8") (pin "2") (pinfunction "2_2") (pintype "passive"))
      (node (ref "Z4") (pin "A") (pinfunction "A_A") (pintype "passive"))
    )
    (net (code "41") (name "Net-(Q2B-G2)") (class "Default")
      (node (ref "Q2") (pin "4") (pinfunction "G2_4") (pintype "passive"))
      (node (ref "R3") (pin "1") (pinfunction "1_1") (pintype "passive"))
      (node (ref "R7") (pin "2") (pinfunction "2_2") (pintype "passive"))
      (node (ref "Z3") (pin "A") (pinfunction "A_A") (pintype "passive"))
    )
    (net (code "42") (name "Net-(Q3-C1)") (class "Default")
      (node (ref "Q3") (pin "6") (pinfunction "C1_6") (pintype "passive"))
      (node (ref "R5") (pin "1") (pinfunction "1_1") (pintype "passive"))
    )
    (net (code "43") (name "Net-(Q4-B1)") (class "Default")
      (node (ref "Q4") (pin "2") (pinfunction "B1_2") (pintype "passive"))
      (node (ref "Q4") (pin "3") (pinfunction "C2_3") (pintype "passive"))
    )
    (net (code "44") (name "Net-(Q4-C1)") (class "Default")
      (node (ref "Q4") (pin "6") (pinfunction "C1_6") (pintype "passive"))
      (node (ref "R6") (pin "1") (pinfunction "1_1") (pintype "passive"))
    )
    (net (code "45") (name "Net-(Q5-C1)") (class "Default")
      (node (ref "Q5") (pin "6") (pinfunction "C1_6") (pintype "passive"))
      (node (ref "R7") (pin "1") (pinfunction "1_1") (pintype "passive"))
    )
    (net (code "46") (name "Net-(Q6-B1)") (class "Default")
      (node (ref "Q6") (pin "2") (pinfunction "B1_2") (pintype "passive"))
      (node (ref "Q6") (pin "3") (pinfunction "C2_3") (pintype "passive"))
    )
    (net (code "47") (name "Net-(Q6-C1)") (class "Default")
      (node (ref "Q6") (pin "6") (pinfunction "C1_6") (pintype "passive"))
      (node (ref "R8") (pin "1") (pinfunction "1_1") (pintype "passive"))
    )
    (net (code "48") (name "Net-(Q7-B)") (class "Default")
      (node (ref "Q7") (pin "1") (pinfunction "B_1") (pintype "passive"))
      (node (ref "R18") (pin "1") (pinfunction "1_1") (pintype "passive"))
    )
    (net (code "49") (name "Net-(Q8-D)") (class "Default")
      (node (ref "Q8") (pin "3") (pinfunction "D_3") (pintype "passive"))
      (node (ref "R30") (pin "2") (pinfunction "2_2") (pintype "passive"))
    )
    (net (code "50") (name "Net-(Q9-D)") (class "Default")
      (node (ref "Q9") (pin "3") (pinfunction "D_3") (pintype "passive"))
      (node (ref "R28") (pin "2") (pinfunction "2_2") (pintype "passive"))
    )
    (net (code "51") (name "Net-(Q10-D)") (class "Default")
      (node (ref "Q10") (pin "3") (pinfunction "D_3") (pintype "passive"))
      (node (ref "R31") (pin "2") (pinfunction "2_2") (pintype "passive"))
    )
    (net (code "52") (name "Net-(Q10-G)") (class "Default")
      (node (ref "Q10") (pin "1") (pinfunction "G_1") (pintype "passive"))
      (node (ref "Q11") (pin "1") (pinfunction "G_1") (pintype "passive"))
      (node (ref "Q7") (pin "3") (pinfunction "C_3") (pintype "passive"))
      (node (ref "Q8") (pin "1") (pinfunction "G_1") (pintype "passive"))
      (node (ref "Q9") (pin "1") (pinfunction "G_1") (pintype "passive"))
      (node (ref "R16") (pin "2") (pinfunction "2_2") (pintype "passive"))
      (node (ref "R19") (pin "2") (pinfunction "2_2") (pintype "passive"))
    )
    (net (code "53") (name "Net-(Q10-S)") (class "Default")
      (node (ref "C17") (pin "2") (pinfunction "2_2") (pintype "passive"))
      (node (ref "Q10") (pin "2") (pinfunction "S_2") (pintype "passive"))
      (node (ref "Q11") (pin "2") (pinfunction "S_2") (pintype "passive"))
      (node (ref "Q8") (pin "2") (pinfunction "S_2") (pintype "passive"))
      (node (ref "Q9") (pin "2") (pinfunction "S_2") (pintype "passive"))
      (node (ref "R22") (pin "2") (pinfunction "2_2") (pintype "passive"))
    )
    (net (code "54") (name "Net-(Q11-D)") (class "Default")
      (node (ref "Q11") (pin "3") (pinfunction "D_3") (pintype "passive"))
      (node (ref "R29") (pin "2") (pinfunction "2_2") (pintype "passive"))
    )
    (net (code "55") (name "Net-(Q12-D)") (class "Default")
      (node (ref "Q12") (pin "3") (pinfunction "D_3") (pintype "passive"))
      (node (ref "R25") (pin "2") (pinfunction "2_2") (pintype "passive"))
    )
    (net (code "56") (name "Net-(Q12-G)") (class "Default")
      (node (ref "Q12") (pin "1") (pinfunction "G_1") (pintype "passive"))
      (node (ref "Q13") (pin "3") (pinfunction "C_3") (pintype "passive"))
      (node (ref "R38") (pin "2") (pinfunction "2_2") (pintype "passive"))
    )
    (net (code "57") (name "Net-(Q13-B)") (class "Default")
      (node (ref "Q13") (pin "1") (pinfunction "B_1") (pintype "passive"))
      (node (ref "R33") (pin "1") (pinfunction "1_1") (pintype "passive"))
    )
    (net (code "58") (name "Net-(U1A-In+)") (class "Default")
      (node (ref "R11") (pin "1") (pinfunction "1_1") (pintype "passive"))
      (node (ref "U1") (pin "1") (pinfunction "In+_1") (pintype "passive"))
    )
    (net (code "59") (name "Net-(U1A-In-)") (class "Default")
      (node (ref "C10") (pin "1") (pinfunction "1_1") (pintype "passive"))
      (node (ref "R14") (pin "1") (pinfunction "1_1") (pintype "passive"))
      (node (ref "R15") (pin "1") (pinfunction "1_1") (pintype "passive"))
      (node (ref "U1") (pin "3") (pinfunction "In-_3") (pintype "passive"))
    )
    (net (code "60") (name "Net-(U2A-A-)") (class "Default")
      (node (ref "C16") (pin "1") (pinfunction "1_1") (pintype "passive"))
      (node (ref "R24") (pin "2") (pinfunction "2_2") (pintype "passive"))
      (node (ref "R25") (pin "1") (pinfunction "1_1") (pintype "passive"))
      (node (ref "R26") (pin "1") (pinfunction "1_1") (pintype "passive"))
      (node (ref "U2") (pin "2") (pinfunction "A-_2") (pintype "passive"))
    )
    (net (code "61") (name "Net-(U3-1Y0)") (class "Default")
      (node (ref "R32") (pin "1") (pinfunction "1_1") (pintype "passive"))
      (node (ref "U3") (pin "12") (pinfunction "1Y0_12") (pintype "passive"))
    )
    (net (code "62") (name "Net-(U3-1Y1)") (class "Default")
      (node (ref "R35") (pin "1") (pinfunction "1_1") (pintype "passive"))
      (node (ref "U3") (pin "14") (pinfunction "1Y1_14") (pintype "passive"))
    )
    (net (code "63") (name "Net-(U3-1Y2)") (class "Default")
      (node (ref "R34") (pin "1") (pinfunction "1_1") (pintype "passive"))
      (node (ref "U3") (pin "15") (pinfunction "1Y2_15") (pintype "passive"))
    )
    (net (code "64") (name "Net-(U3-1Y3)") (class "Default")
      (node (ref "R36") (pin "1") (pinfunction "1_1") (pintype "passive"))
      (node (ref "U3") (pin "11") (pinfunction "1Y3_11") (pintype "passive"))
    )
    (net (code "65") (name "Vnn") (class "Default")
      (node (ref "C9") (pin "2") (pinfunction "2_2") (pintype "passive"))
      (node (ref "R14") (pin "2") (pinfunction "2_2") (pintype "passive"))
      (node (ref "R17") (pin "1") (pinfunction "1_1") (pintype "passive"))
    )
    (net (code "66") (name "Vpp") (class "Default")
      (node (ref "Q1") (pin "1") (pinfunction "S1_1") (pintype "passive"))
      (node (ref "Q1") (pin "3") (pinfunction "S2_3") (pintype "passive"))
      (node (ref "Q2") (pin "1") (pinfunction "S1_1") (pintype "passive"))
      (node (ref "Q2") (pin "3") (pinfunction "S2_3") (pintype "passive"))
      (node (ref "R1") (pin "2") (pinfunction "2_2") (pintype "passive"))
      (node (ref "R2") (pin "2") (pinfunction "2_2") (pintype "passive"))
      (node (ref "R3") (pin "2") (pinfunction "2_2") (pintype "passive"))
      (node (ref "R4") (pin "2") (pinfunction "2_2") (pintype "passive"))
      (node (ref "Z1") (pin "K") (pinfunction "K_K") (pintype "passive"))
      (node (ref "Z2") (pin "K") (pinfunction "K_K") (pintype "passive"))
      (node (ref "Z3") (pin "K") (pinfunction "K_K") (pintype "passive"))
      (node (ref "Z4") (pin "K") (pinfunction "K_K") (pintype "passive"))
    )
    (net (code "67") (name "unconnected-(U3-2Y0-Pad1)") (class "Default")
      (node (ref "U3") (pin "1") (pinfunction "2Y0_1") (pintype "passive"))
    )
    (net (code "68") (name "unconnected-(U3-2Y1-Pad5)") (class "Default")
      (node (ref "U3") (pin "5") (pinfunction "2Y1_5") (pintype "passive"))
    )
    (net (code "69") (name "unconnected-(U3-2Y2-Pad2)") (class "Default")
      (node (ref "U3") (pin "2") (pinfunction "2Y2_2") (pintype "passive"))
    )
    (net (code "70") (name "unconnected-(U3-2Y3-Pad4)") (class "Default")
      (node (ref "U3") (pin "4") (pinfunction "2Y3_4") (pintype "passive"))
    )
    (net (code "71") (name "unconnected-(U3-2Z-Pad3)") (class "Default")
      (node (ref "U3") (pin "3") (pinfunction "2Z_3") (pintype "passive"))
    )
    (net (code "72") (name "unconnected-(Z5-PadNC)") (class "Default")
      (node (ref "Z5") (pin "NC") (pinfunction "NC_NC") (pintype "passive"))
    )
  )
)
